# simple-loop1.net
KiCad netlist of a schematic drawn in EAGLE
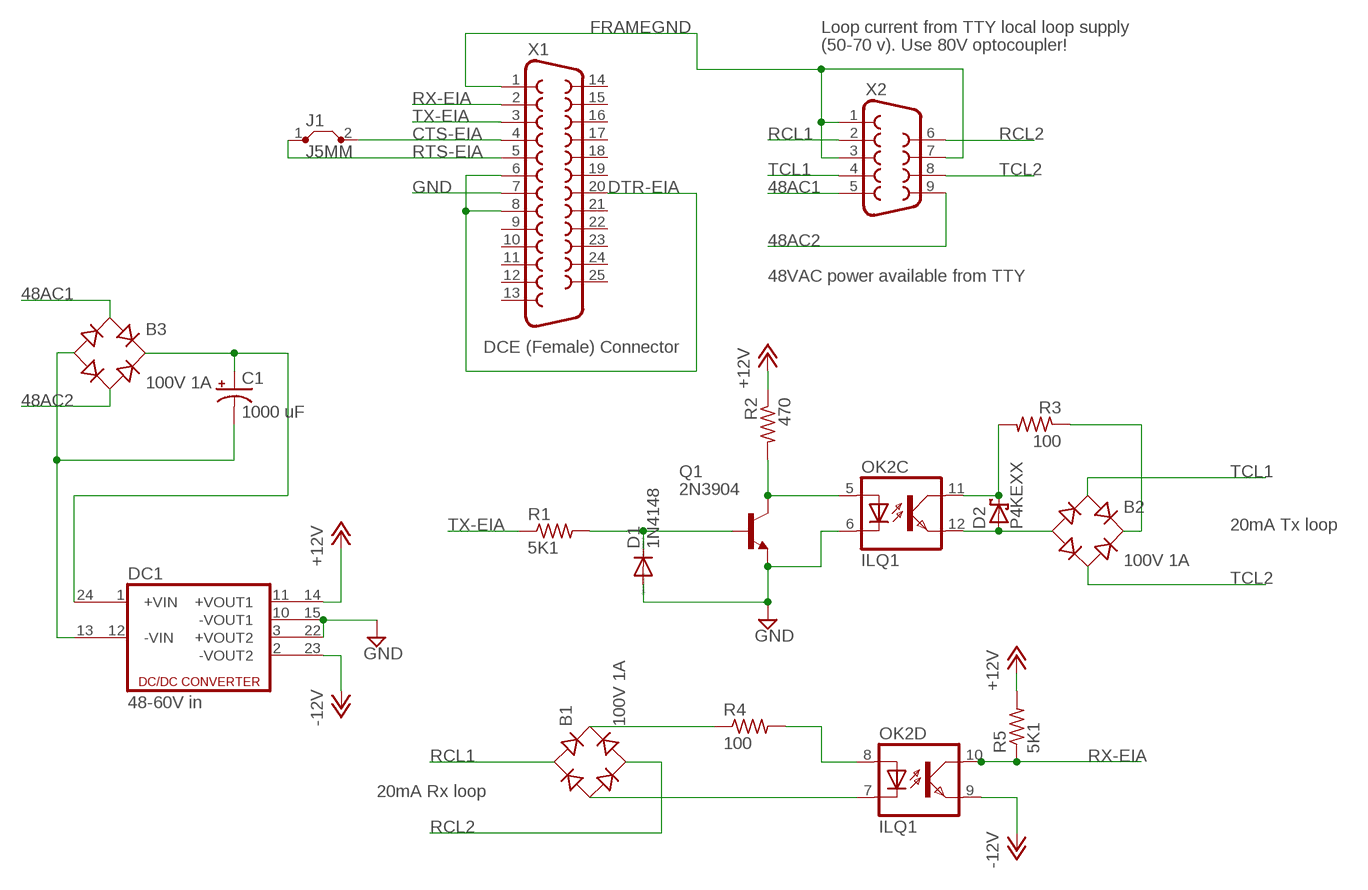
[diagram p0: schematic, sheet 1]

(export (version "E")
  (design (tool "Eeschema 10.0.6"))
  (components
    (comp (ref "B1")
      (value "100V 1A")
      (footprint "eagle-import:RB1A")
      (libsource (lib "eagle-import") (part "RB1A"))
    )
    (comp (ref "B2")
      (value "100V 1A")
      (footprint "eagle-import:RB1A")
      (libsource (lib "eagle-import") (part "RB1A"))
    )
    (comp (ref "B3")
      (value "100V 1A")
      (footprint "eagle-import:RB1A")
      (libsource (lib "eagle-import") (part "RB1A"))
    )
    (comp (ref "C1")
      (value "1000 uF")
      (footprint "eagle-import:E7,5-18")
      (libsource (lib "eagle-import") (part "CPOL-USE7.5-18"))
    )
    (comp (ref "D1")
      (value "1N4148")
      (footprint "eagle-import:DO35-10")
      (libsource (lib "eagle-import") (part "1N4148DO35-10"))
    )
    (comp (ref "D2")
      (value "P4KEXX")
      (footprint "eagle-import:DO41-10")
      (libsource (lib "eagle-import") (part "P4KEXX"))
    )
    (comp (ref "DC1")
      (value "48-60V in")
      (footprint "eagle-import:DCW")
      (libsource (lib "eagle-import") (part "DCW2U"))
    )
    (comp (ref "J1")
      (value "J5MM")
      (footprint "eagle-import:05")
      (libsource (lib "eagle-import") (part "J5MM"))
    )
    (comp (ref "OK2")
      (value "ILQ1")
      (footprint "eagle-import:DIL16")
      (fields (field (name "MF") "VISHAY/TELEFUNKEN"))
      (libsource (lib "eagle-import") (part "ILQ1"))
    )
    (comp (ref "Q1")
      (value "2N3904")
      (footprint "eagle-import:TO92")
      (libsource (lib "eagle-import") (part "2N3904"))
    )
    (comp (ref "R1")
      (value "5K1")
      (footprint "eagle-import:0207_10")
      (libsource (lib "eagle-import") (part "R-US_0207/10"))
    )
    (comp (ref "R2")
      (value "470")
      (footprint "eagle-import:0207_10")
      (libsource (lib "eagle-import") (part "R-US_0207/10"))
    )
    (comp (ref "R3")
      (value "100")
      (footprint "eagle-import:0207_10")
      (libsource (lib "eagle-import") (part "R-US_0207/10"))
    )
    (comp (ref "R4")
      (value "100")
      (footprint "eagle-import:0207_10")
      (libsource (lib "eagle-import") (part "R-US_0207/10"))
    )
    (comp (ref "R5")
      (value "5K1")
      (footprint "eagle-import:0207_10")
      (libsource (lib "eagle-import") (part "R-US_0207/10"))
    )
    (comp (ref "X1")
      (value "F25H")
      (footprint "eagle-import:F25H")
      (libsource (lib "eagle-import") (part "F25H"))
    )
    (comp (ref "X2")
      (value "F09H")
      (footprint "eagle-import:F09H")
      (libsource (lib "eagle-import") (part "F09H"))
    )
  )
  (nets
    (net (code "1") (name "+12V") (class "Default")
      (node (ref "DC1") (pin "14") (pinfunction "+VOUT_14") (pintype "passive"))
      (node (ref "R2") (pin "1") (pinfunction "1_1") (pintype "passive"))
      (node (ref "R5") (pin "2") (pinfunction "2_2") (pintype "passive"))
    )
    (net (code "2") (name "-12V") (class "Default")
      (node (ref "DC1") (pin "23") (pinfunction "-VOUT_23") (pintype "passive"))
      (node (ref "OK2") (pin "9") (pinfunction "EMIT_9") (pintype "passive"))
    )
    (net (code "3") (name "/48AC1") (class "Default")
      (node (ref "B3") (pin "AC1") (pinfunction "AC1_AC1") (pintype "passive"))
      (node (ref "X2") (pin "5") (pinfunction "5_5") (pintype "passive"))
    )
    (net (code "4") (name "/48AC2") (class "Default")
      (node (ref "B3") (pin "AC2") (pinfunction "AC2_AC2") (pintype "passive"))
      (node (ref "X2") (pin "9") (pinfunction "9_9") (pintype "passive"))
    )
    (net (code "5") (name "/CTS-EIA") (class "Default")
      (node (ref "J1") (pin "2") (pinfunction "2_2") (pintype "passive"))
      (node (ref "X1") (pin "4") (pinfunction "4_4") (pintype "passive"))
    )
    (net (code "6") (name "/DTR-EIA") (class "Default")
      (node (ref "X1") (pin "20") (pinfunction "20_20") (pintype "passive"))
      (node (ref "X1") (pin "6") (pinfunction "6_6") (pintype "passive"))
      (node (ref "X1") (pin "8") (pinfunction "8_8") (pintype "passive"))
    )
    (net (code "7") (name "/FRAMEGND") (class "Default")
      (node (ref "X1") (pin "1") (pinfunction "1_1") (pintype "passive"))
      (node (ref "X2") (pin "1") (pinfunction "1_1") (pintype "passive"))
      (node (ref "X2") (pin "3") (pinfunction "3_3") (pintype "passive"))
      (node (ref "X2") (pin "7") (pinfunction "7_7") (pintype "passive"))
    )
    (net (code "8") (name "/RCL1") (class "Default")
      (node (ref "B1") (pin "AC1") (pinfunction "AC1_AC1") (pintype "passive"))
      (node (ref "X2") (pin "2") (pinfunction "2_2") (pintype "passive"))
    )
    (net (code "9") (name "/RCL2") (class "Default")
      (node (ref "B1") (pin "AC2") (pinfunction "AC2_AC2") (pintype "passive"))
      (node (ref "X2") (pin "6") (pinfunction "6_6") (pintype "passive"))
    )
    (net (code "10") (name "/RTS-EIA") (class "Default")
      (node (ref "J1") (pin "1") (pinfunction "1_1") (pintype "passive"))
      (node (ref "X1") (pin "5") (pinfunction "5_5") (pintype "passive"))
    )
    (net (code "11") (name "/RX-EIA") (class "Default")
      (node (ref "OK2") (pin "10") (pinfunction "COL_10") (pintype "passive"))
      (node (ref "R5") (pin "1") (pinfunction "1_1") (pintype "passive"))
      (node (ref "X1") (pin "2") (pinfunction "2_2") (pintype "passive"))
    )
    (net (code "12") (name "/TCL1") (class "Default")
      (node (ref "B2") (pin "AC1") (pinfunction "AC1_AC1") (pintype "passive"))
      (node (ref "X2") (pin "4") (pinfunction "4_4") (pintype "passive"))
    )
    (net (code "13") (name "/TCL2") (class "Default")
      (node (ref "B2") (pin "AC2") (pinfunction "AC2_AC2") (pintype "passive"))
      (node (ref "X2") (pin "8") (pinfunction "8_8") (pintype "passive"))
    )
    (net (code "14") (name "/TX-EIA") (class "Default")
      (node (ref "R1") (pin "1") (pinfunction "1_1") (pintype "passive"))
      (node (ref "X1") (pin "3") (pinfunction "3_3") (pintype "passive"))
    )
    (net (code "15") (name "GND") (class "Default")
      (node (ref "D1") (pin "A") (pinfunction "A_A") (pintype "passive"))
      (node (ref "DC1") (pin "15") (pinfunction "-VOUT_15") (pintype "passive"))
      (node (ref "DC1") (pin "22") (pinfunction "+VOUT_22") (pintype "passive"))
      (node (ref "OK2") (pin "6") (pinfunction "C_6") (pintype "passive"))
      (node (ref "Q1") (pin "3") (pinfunction "E_3") (pintype "passive"))
      (node (ref "X1") (pin "7") (pinfunction "7_7") (pintype "passive"))
    )
    (net (code "16") (name "Net-(B1-Pad+)") (class "Default")
      (node (ref "B1") (pin "+") (pinfunction "+_+") (pintype "passive"))
      (node (ref "R4") (pin "1") (pinfunction "1_1") (pintype "passive"))
    )
    (net (code "17") (name "Net-(B2-Pad+)") (class "Default")
      (node (ref "B2") (pin "+") (pinfunction "+_+") (pintype "passive"))
      (node (ref "R3") (pin "1") (pinfunction "1_1") (pintype "passive"))
    )
    (net (code "18") (name "Net-(DC1-+VIN1)") (class "Default")
      (node (ref "B3") (pin "+") (pinfunction "+_+") (pintype "passive"))
      (node (ref "C1") (pin "+") (pinfunction "+_+") (pintype "passive"))
      (node (ref "DC1") (pin "24") (pinfunction "+VIN1_24") (pintype "passive"))
    )
    (net (code "19") (name "Net-(DC1--VIN1)") (class "Default")
      (node (ref "B3") (pin "-") (pinfunction "-_-") (pintype "passive"))
      (node (ref "C1") (pin "-") (pinfunction "-_-") (pintype "passive"))
      (node (ref "DC1") (pin "13") (pinfunction "-VIN1_13") (pintype "passive"))
    )
    (net (code "20") (name "Net-(OK2C-A)") (class "Default")
      (node (ref "OK2") (pin "5") (pinfunction "A_5") (pintype "passive"))
      (node (ref "Q1") (pin "1") (pinfunction "C_1") (pintype "passive"))
      (node (ref "R2") (pin "2") (pinfunction "2_2") (pintype "passive"))
    )
    (net (code "21") (name "Net-(OK2C-COL)") (class "Default")
      (node (ref "D2") (pin "C") (pinfunction "C_C") (pintype "passive"))
      (node (ref "OK2") (pin "11") (pinfunction "COL_11") (pintype "passive"))
      (node (ref "R3") (pin "2") (pinfunction "2_2") (pintype "passive"))
    )
    (net (code "22") (name "Net-(OK2C-EMIT)") (class "Default")
      (node (ref "B2") (pin "-") (pinfunction "-_-") (pintype "passive"))
      (node (ref "D2") (pin "A") (pinfunction "A_A") (pintype "passive"))
      (node (ref "OK2") (pin "12") (pinfunction "EMIT_12") (pintype "passive"))
    )
    (net (code "23") (name "Net-(OK2D-A)") (class "Default")
      (node (ref "OK2") (pin "8") (pinfunction "A_8") (pintype "passive"))
      (node (ref "R4") (pin "2") (pinfunction "2_2") (pintype "passive"))
    )
    (net (code "24") (name "Net-(OK2D-C)") (class "Default")
      (node (ref "B1") (pin "-") (pinfunction "-_-") (pintype "passive"))
      (node (ref "OK2") (pin "7") (pinfunction "C_7") (pintype "passive"))
    )
    (net (code "25") (name "Net-(Q1-B)") (class "Default")
      (node (ref "D1") (pin "C") (pinfunction "C_C") (pintype "passive"))
      (node (ref "Q1") (pin "2") (pinfunction "B_2") (pintype "passive"))
      (node (ref "R1") (pin "2") (pinfunction "2_2") (pintype "passive"))
    )
    (net (code "26") (name "unconnected-(DC1-+VIN-Pad1)") (class "Default")
      (node (ref "DC1") (pin "1") (pinfunction "+VIN_1") (pintype "passive"))
    )
    (net (code "27") (name "unconnected-(DC1-+VOUT1-Pad11)") (class "Default")
      (node (ref "DC1") (pin "11") (pinfunction "+VOUT1_11") (pintype "passive"))
    )
    (net (code "28") (name "unconnected-(DC1-+VOUT2-Pad3)") (class "Default")
      (node (ref "DC1") (pin "3") (pinfunction "+VOUT2_3") (pintype "passive"))
    )
    (net (code "29") (name "unconnected-(DC1--VIN-Pad12)") (class "Default")
      (node (ref "DC1") (pin "12") (pinfunction "-VIN_12") (pintype "passive"))
    )
    (net (code "30") (name "unconnected-(DC1--VOUT1-Pad10)") (class "Default")
      (node (ref "DC1") (pin "10") (pinfunction "-VOUT1_10") (pintype "passive"))
    )
    (net (code "31") (name "unconnected-(DC1--VOUT2-Pad2)") (class "Default")
      (node (ref "DC1") (pin "2") (pinfunction "-VOUT2_2") (pintype "passive"))
    )
    (net (code "32") (name "unconnected-(X1-Pad9)") (class "Default")
      (node (ref "X1") (pin "9") (pinfunction "9_9") (pintype "passive"))
    )
    (net (code "33") (name "unconnected-(X1-Pad10)") (class "Default")
      (node (ref "X1") (pin "10") (pinfunction "10_10") (pintype "passive"))
    )
    (net (code "34") (name "unconnected-(X1-Pad11)") (class "Default")
      (node (ref "X1") (pin "11") (pinfunction "11_11") (pintype "passive"))
    )
    (net (code "35") (name "unconnected-(X1-Pad12)") (class "Default")
      (node (ref "X1") (pin "12") (pinfunction "12_12") (pintype "passive"))
    )
    (net (code "36") (name "unconnected-(X1-Pad13)") (class "Default")
      (node (ref "X1") (pin "13") (pinfunction "13_13") (pintype "passive"))
    )
    (net (code "37") (name "unconnected-(X1-Pad14)") (class "Default")
      (node (ref "X1") (pin "14") (pinfunction "14_14") (pintype "passive"))
    )
    (net (code "38") (name "unconnected-(X1-Pad15)") (class "Default")
      (node (ref "X1") (pin "15") (pinfunction "15_15") (pintype "passive"))
    )
    (net (code "39") (name "unconnected-(X1-Pad16)") (class "Default")
      (node (ref "X1") (pin "16") (pinfunction "16_16") (pintype "passive"))
    )
    (net (code "40") (name "unconnected-(X1-Pad17)") (class "Default")
      (node (ref "X1") (pin "17") (pinfunction "17_17") (pintype "passive"))
    )
    (net (code "41") (name "unconnected-(X1-Pad18)") (class "Default")
      (node (ref "X1") (pin "18") (pinfunction "18_18") (pintype "passive"))
    )
    (net (code "42") (name "unconnected-(X1-Pad19)") (class "Default")
      (node (ref "X1") (pin "19") (pinfunction "19_19") (pintype "passive"))
    )
    (net (code "43") (name "unconnected-(X1-Pad21)") (class "Default")
      (node (ref "X1") (pin "21") (pinfunction "21_21") (pintype "passive"))
    )
    (net (code "44") (name "unconnected-(X1-Pad22)") (class "Default")
      (node (ref "X1") (pin "22") (pinfunction "22_22") (pintype "passive"))
    )
    (net (code "45") (name "unconnected-(X1-Pad23)") (class "Default")
      (node (ref "X1") (pin "23") (pinfunction "23_23") (pintype "passive"))
    )
    (net (code "46") (name "unconnected-(X1-Pad24)") (class "Default")
      (node (ref "X1") (pin "24") (pinfunction "24_24") (pintype "passive"))
    )
    (net (code "47") (name "unconnected-(X1-Pad25)") (class "Default")
      (node (ref "X1") (pin "25") (pinfunction "25_25") (pintype "passive"))
    )
  )
)
